# W5500.net
KiCad netlist of a schematic drawn in Altium Designer
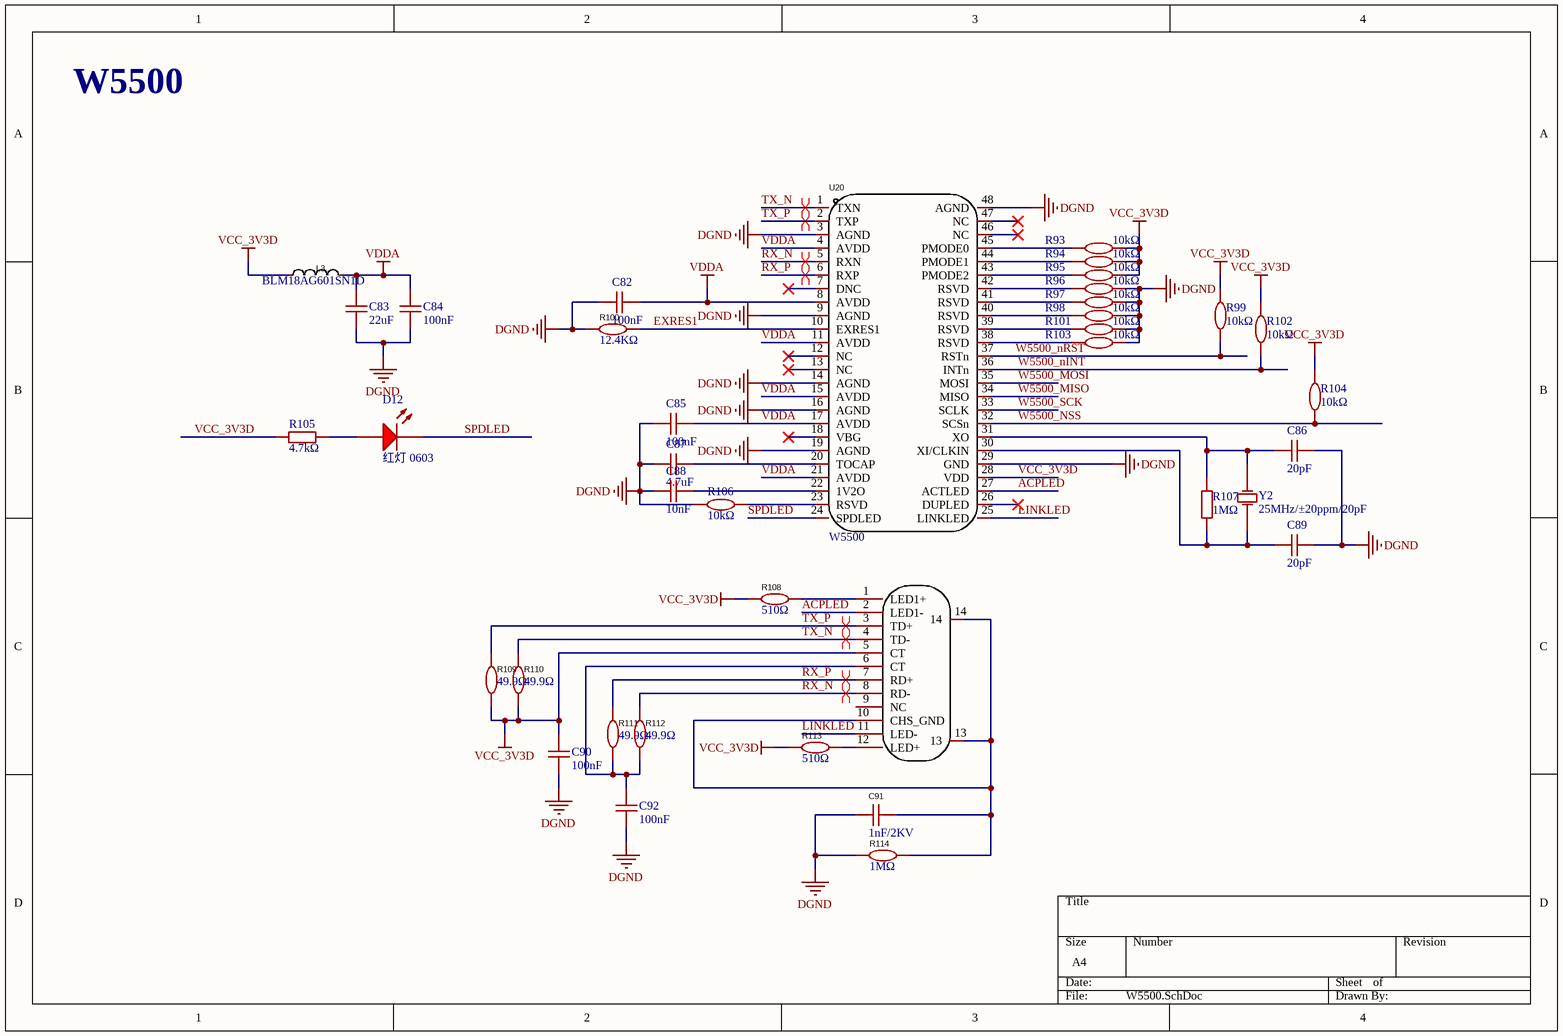
[diagram p0: W5500.SchDoc]

(export (version "E")
  (design (tool "Eeschema 10.0.6"))
  (components
    (comp (ref "C82")
      (value "100nF")
      (footprint "C0402")
      (description "贴片电容,X7R")
      (libsource (lib "XG_DW_POCT_2K10LED_3") (part "100nF/50V,C0402"))
    )
    (comp (ref "C83")
      (value "22uF")
      (footprint "C0603")
      (description "贴片电容,X7R")
      (libsource (lib "XG_DW_POCT_2K10LED_3") (part "22uF/50V,C0603"))
    )
    (comp (ref "C84")
      (value "100nF")
      (footprint "C0402")
      (description "贴片电容,X7R")
      (libsource (lib "XG_DW_POCT_2K10LED_3") (part "100nF/50V,C0402"))
    )
    (comp (ref "C85")
      (value "100nF")
      (footprint "C0402")
      (description "贴片电容,X7R")
      (libsource (lib "XG_DW_POCT_2K10LED_3") (part "100nF/50V,C0402"))
    )
    (comp (ref "C86")
      (value "20pF")
      (footprint "C0603")
      (description "贴片电容,X7R")
      (libsource (lib "XG_DW_POCT_2K10LED_3") (part "20pF/50V,C0603"))
    )
    (comp (ref "C87")
      (value "4.7uF")
      (footprint "C0402")
      (description "贴片电容,X7R")
      (libsource (lib "XG_DW_POCT_2K10LED_3") (part "4.7uF/50V,C0402"))
    )
    (comp (ref "C88")
      (value "10nF")
      (footprint "C0402")
      (description "贴片电容,X7R")
      (libsource (lib "XG_DW_POCT_2K10LED_3") (part "10nF/50V,C0402"))
    )
    (comp (ref "C89")
      (value "20pF")
      (footprint "C0603")
      (description "贴片电容,X7R")
      (libsource (lib "XG_DW_POCT_2K10LED_3") (part "20pF/50V,C0603"))
    )
    (comp (ref "C90")
      (value "100nF")
      (footprint "C0402")
      (description "贴片电容,X7R")
      (libsource (lib "XG_DW_POCT_2K10LED_3") (part "100nF/50V,C0402"))
    )
    (comp (ref "C91")
      (value "1nF/2KV")
      (footprint "C1206")
      (description "贴片电容,X7R")
      (libsource (lib "XG_DW_POCT_2K10LED_3") (part "1nF/2KV,C1206"))
    )
    (comp (ref "C92")
      (value "100nF")
      (footprint "C0402")
      (description "贴片电容,X7R")
      (libsource (lib "XG_DW_POCT_2K10LED_3") (part "100nF/50V,C0402"))
    )
    (comp (ref "D12")
      (value "红灯 0603")
      (footprint "LED_0603")
      (description "发光二极管")
      (libsource (lib "XG_DW_POCT_2K10LED_3") (part "红灯 0603"))
    )
    (comp (ref "L3")
      (value "BLM18AG601SN1D")
      (footprint "L0603")
      (fields (field (name "MANUFACTURER") "muRata(村田)") (field (name "TOLERANCE") "±25%"))
      (libsource (lib "altium-import") (part "root_0_BLM18AG601SN1D_"))
    )
    (comp (ref "R93")
      (value "10kΩ")
      (footprint "R0402")
      (description "电阻类型:厚膜电阻;阻值:10kΩ;精度:±1%;功率:100mW;最大工作电压:75V;温度系数:±100ppm/℃;")
      (libsource (lib "XG_DW_POCT_2K10LED_3") (part "10kΩ,R0402"))
    )
    (comp (ref "R94")
      (value "10kΩ")
      (footprint "R0402")
      (description "电阻类型:厚膜电阻;阻值:10kΩ;精度:±1%;功率:100mW;最大工作电压:75V;温度系数:±100ppm/℃;")
      (libsource (lib "XG_DW_POCT_2K10LED_3") (part "10kΩ,R0402"))
    )
    (comp (ref "R95")
      (value "10kΩ")
      (footprint "R0402")
      (description "电阻类型:厚膜电阻;阻值:10kΩ;精度:±1%;功率:100mW;最大工作电压:75V;温度系数:±100ppm/℃;")
      (libsource (lib "XG_DW_POCT_2K10LED_3") (part "10kΩ,R0402"))
    )
    (comp (ref "R96")
      (value "10kΩ")
      (footprint "R0402")
      (description "电阻类型:厚膜电阻;阻值:10kΩ;精度:±1%;功率:100mW;最大工作电压:75V;温度系数:±100ppm/℃;")
      (libsource (lib "XG_DW_POCT_2K10LED_3") (part "10kΩ,R0402"))
    )
    (comp (ref "R97")
      (value "10kΩ")
      (footprint "R0402")
      (description "电阻类型:厚膜电阻;阻值:10kΩ;精度:±1%;功率:100mW;最大工作电压:75V;温度系数:±100ppm/℃;")
      (libsource (lib "XG_DW_POCT_2K10LED_3") (part "10kΩ,R0402"))
    )
    (comp (ref "R98")
      (value "10kΩ")
      (footprint "R0402")
      (description "电阻类型:厚膜电阻;阻值:10kΩ;精度:±1%;功率:100mW;最大工作电压:75V;温度系数:±100ppm/℃;")
      (libsource (lib "XG_DW_POCT_2K10LED_3") (part "10kΩ,R0402"))
    )
    (comp (ref "R99")
      (value "10kΩ")
      (footprint "R0402")
      (description "电阻类型:厚膜电阻;阻值:10kΩ;精度:±1%;功率:100mW;最大工作电压:75V;温度系数:±100ppm/℃;")
      (libsource (lib "XG_DW_POCT_2K10LED_3") (part "10kΩ,R0402"))
    )
    (comp (ref "R100")
      (value "12.4KΩ")
      (footprint "R0402")
      (description "贴片电阻12.4KΩ;1%")
      (libsource (lib "XG_DW_POCT_2K10LED_3") (part "12.4KΩ,R0402"))
    )
    (comp (ref "R101")
      (value "10kΩ")
      (footprint "R0402")
      (description "电阻类型:厚膜电阻;阻值:10kΩ;精度:±1%;功率:100mW;最大工作电压:75V;温度系数:±100ppm/℃;")
      (libsource (lib "XG_DW_POCT_2K10LED_3") (part "10kΩ,R0402"))
    )
    (comp (ref "R102")
      (value "10kΩ")
      (footprint "R0402")
      (description "电阻类型:厚膜电阻;阻值:10kΩ;精度:±1%;功率:100mW;最大工作电压:75V;温度系数:±100ppm/℃;")
      (libsource (lib "XG_DW_POCT_2K10LED_3") (part "10kΩ,R0402"))
    )
    (comp (ref "R103")
      (value "10kΩ")
      (footprint "R0402")
      (description "电阻类型:厚膜电阻;阻值:10kΩ;精度:±1%;功率:100mW;最大工作电压:75V;温度系数:±100ppm/℃;")
      (libsource (lib "XG_DW_POCT_2K10LED_3") (part "10kΩ,R0402"))
    )
    (comp (ref "R104")
      (value "10kΩ")
      (footprint "R0402")
      (description "电阻类型:厚膜电阻;阻值:10kΩ;精度:±1%;功率:100mW;最大工作电压:75V;温度系数:±100ppm/℃;")
      (libsource (lib "XG_DW_POCT_2K10LED_3") (part "10kΩ,R0402"))
    )
    (comp (ref "R105")
      (value "4.7kΩ")
      (footprint "R0603")
      (description "贴片电阻")
      (libsource (lib "XG_DW_POCT_2K10LED_3") (part "4.7kΩ,R0603"))
    )
    (comp (ref "R106")
      (value "10kΩ")
      (footprint "R0402")
      (description "电阻类型:厚膜电阻;阻值:10kΩ;精度:±1%;功率:100mW;最大工作电压:75V;温度系数:±100ppm/℃;")
      (libsource (lib "XG_DW_POCT_2K10LED_3") (part "10kΩ,R0402"))
    )
    (comp (ref "R107")
      (value "1MΩ")
      (footprint "R0603")
      (description "贴片电阻")
      (libsource (lib "XG_DW_POCT_2K10LED_3") (part "1MΩ,R0603"))
    )
    (comp (ref "R108")
      (value "510Ω")
      (footprint "R0402")
      (description "贴片电阻")
      (libsource (lib "XG_DW_POCT_2K10LED_3") (part "510Ω,R0402"))
    )
    (comp (ref "R109")
      (value "49.9Ω")
      (footprint "R0402")
      (description "贴片电阻49.9R;1%")
      (libsource (lib "XG_DW_POCT_2K10LED_3") (part "49.9Ω,R0402"))
    )
    (comp (ref "R110")
      (value "49.9Ω")
      (footprint "R0402")
      (description "贴片电阻49.9R;1%")
      (libsource (lib "XG_DW_POCT_2K10LED_3") (part "49.9Ω,R0402"))
    )
    (comp (ref "R111")
      (value "49.9Ω")
      (footprint "R0402")
      (description "贴片电阻49.9R;1%")
      (libsource (lib "XG_DW_POCT_2K10LED_3") (part "49.9Ω,R0402"))
    )
    (comp (ref "R112")
      (value "49.9Ω")
      (footprint "R0402")
      (description "贴片电阻49.9R;1%")
      (libsource (lib "XG_DW_POCT_2K10LED_3") (part "49.9Ω,R0402"))
    )
    (comp (ref "R113")
      (value "510Ω")
      (footprint "R0402")
      (description "贴片电阻")
      (libsource (lib "XG_DW_POCT_2K10LED_3") (part "510Ω,R0402"))
    )
    (comp (ref "R114")
      (value "1MΩ")
      (footprint "R0402")
      (description "电阻类型:厚膜电阻;阻值:1MΩ;精度:±1%;功率:100mW;最大工作电压:75V;温度系数:±100ppm/℃;")
      (libsource (lib "XG_DW_POCT_2K10LED_3") (part "1MΩ,R0402"))
    )
    (comp (ref "RJ1")
      (value "HR961160C")
      (footprint "RJ45-SMD_HR961160C")
      (libsource (lib "XG_DW_POCT_2K10LED_3") (part "HR961160C"))
    )
    (comp (ref "U20")
      (value "W5500")
      (footprint "LQFP-48_L7.0-W7.0-P0.50-LS9.0-BL")
      (libsource (lib "XG_DW_POCT_2K10LED_3") (part "W5500"))
    )
    (comp (ref "Y2")
      (value "25MHz/±20ppm/20pF")
      (footprint "SMD-5032_2P")
      (description "X503225MSB2GI;无源晶振")
      (libsource (lib "XG_DW_POCT_2K10LED_3") (part "25MHz/±20ppm/20pF,SMD5032"))
    )
  )
  (nets
    (net (code "1") (name "/ACPLED") (class "Default")
      (node (ref "RJ1") (pin "2") (pinfunction "LED1-_2") (pintype "passive"))
      (node (ref "U20") (pin "27") (pinfunction "ACTLED_27") (pintype "passive"))
    )
    (net (code "2") (name "/EXRES1") (class "Default")
      (node (ref "R100") (pin "2") (pinfunction "2_2") (pintype "passive"))
      (node (ref "U20") (pin "10") (pinfunction "EXRES1_10") (pintype "passive"))
    )
    (net (code "3") (name "/LINKLED") (class "Default")
      (node (ref "RJ1") (pin "11") (pinfunction "LED-_11") (pintype "passive"))
      (node (ref "U20") (pin "25") (pinfunction "LINKLED_25") (pintype "passive"))
    )
    (net (code "4") (name "/RX_N") (class "Default")
      (node (ref "R112") (pin "2") (pinfunction "2_2") (pintype "passive"))
      (node (ref "RJ1") (pin "8") (pinfunction "RD-_8") (pintype "passive"))
      (node (ref "U20") (pin "5") (pinfunction "RXN_5") (pintype "passive"))
    )
    (net (code "5") (name "/RX_P") (class "Default")
      (node (ref "R111") (pin "2") (pinfunction "2_2") (pintype "passive"))
      (node (ref "RJ1") (pin "7") (pinfunction "RD+_7") (pintype "passive"))
      (node (ref "U20") (pin "6") (pinfunction "RXP_6") (pintype "passive"))
    )
    (net (code "6") (name "/SPDLED") (class "Default")
      (node (ref "D12") (pin "K") (pinfunction "K_K") (pintype "passive"))
      (node (ref "U20") (pin "24") (pinfunction "SPDLED_24") (pintype "passive"))
    )
    (net (code "7") (name "/TX_N") (class "Default")
      (node (ref "R110") (pin "2") (pinfunction "2_2") (pintype "passive"))
      (node (ref "RJ1") (pin "4") (pinfunction "TD-_4") (pintype "passive"))
      (node (ref "U20") (pin "1") (pinfunction "TXN_1") (pintype "passive"))
    )
    (net (code "8") (name "/TX_P") (class "Default")
      (node (ref "R109") (pin "2") (pinfunction "2_2") (pintype "passive"))
      (node (ref "RJ1") (pin "3") (pinfunction "TD+_3") (pintype "passive"))
      (node (ref "U20") (pin "2") (pinfunction "TXP_2") (pintype "passive"))
    )
    (net (code "9") (name "/W5500_MISO") (class "Default")
      (node (ref "U20") (pin "34") (pinfunction "MISO_34") (pintype "passive"))
    )
    (net (code "10") (name "/W5500_MOSI") (class "Default")
      (node (ref "U20") (pin "35") (pinfunction "MOSI_35") (pintype "passive"))
    )
    (net (code "11") (name "/W5500_NSS") (class "Default")
      (node (ref "R104") (pin "2") (pinfunction "2_2") (pintype "passive"))
      (node (ref "U20") (pin "32") (pinfunction "SCSn_32") (pintype "passive"))
    )
    (net (code "12") (name "/W5500_SCK") (class "Default")
      (node (ref "U20") (pin "33") (pinfunction "SCLK_33") (pintype "passive"))
    )
    (net (code "13") (name "/W5500_nINT") (class "Default")
      (node (ref "R102") (pin "2") (pinfunction "2_2") (pintype "passive"))
      (node (ref "U20") (pin "36") (pinfunction "INTn_36") (pintype "passive"))
    )
    (net (code "14") (name "/W5500_nRST") (class "Default")
      (node (ref "R99") (pin "2") (pinfunction "2_2") (pintype "passive"))
      (node (ref "U20") (pin "37") (pinfunction "RSTn_37") (pintype "passive"))
    )
    (net (code "15") (name "DGND") (class "Default")
      (node (ref "C82") (pin "1") (pinfunction "1_1") (pintype "passive"))
      (node (ref "C83") (pin "1") (pinfunction "1_1") (pintype "passive"))
      (node (ref "C84") (pin "1") (pinfunction "1_1") (pintype "passive"))
      (node (ref "C85") (pin "1") (pinfunction "1_1") (pintype "passive"))
      (node (ref "C86") (pin "2") (pinfunction "2_2") (pintype "passive"))
      (node (ref "C87") (pin "1") (pinfunction "1_1") (pintype "passive"))
      (node (ref "C88") (pin "1") (pinfunction "1_1") (pintype "passive"))
      (node (ref "C89") (pin "2") (pinfunction "2_2") (pintype "passive"))
      (node (ref "C90") (pin "1") (pinfunction "1_1") (pintype "passive"))
      (node (ref "C91") (pin "1") (pinfunction "1_1") (pintype "passive"))
      (node (ref "C92") (pin "1") (pinfunction "1_1") (pintype "passive"))
      (node (ref "R100") (pin "1") (pinfunction "1_1") (pintype "passive"))
      (node (ref "R101") (pin "1") (pinfunction "1_1") (pintype "passive"))
      (node (ref "R103") (pin "1") (pinfunction "1_1") (pintype "passive"))
      (node (ref "R106") (pin "2") (pinfunction "2_2") (pintype "passive"))
      (node (ref "R114") (pin "1") (pinfunction "1_1") (pintype "passive"))
      (node (ref "R96") (pin "1") (pinfunction "1_1") (pintype "passive"))
      (node (ref "R97") (pin "1") (pinfunction "1_1") (pintype "passive"))
      (node (ref "R98") (pin "1") (pinfunction "1_1") (pintype "passive"))
      (node (ref "U20") (pin "14") (pinfunction "AGND_14") (pintype "passive"))
      (node (ref "U20") (pin "16") (pinfunction "AGND_16") (pintype "passive"))
      (node (ref "U20") (pin "19") (pinfunction "AGND_19") (pintype "passive"))
      (node (ref "U20") (pin "29") (pinfunction "GND_29") (pintype "passive"))
      (node (ref "U20") (pin "3") (pinfunction "AGND_3") (pintype "passive"))
      (node (ref "U20") (pin "48") (pinfunction "AGND_48") (pintype "passive"))
      (node (ref "U20") (pin "9") (pinfunction "AGND_9") (pintype "passive"))
    )
    (net (code "16") (name "Net-(C92-Pad2)") (class "Default")
      (node (ref "C92") (pin "2") (pinfunction "2_2") (pintype "passive"))
      (node (ref "R111") (pin "1") (pinfunction "1_1") (pintype "passive"))
      (node (ref "R112") (pin "1") (pinfunction "1_1") (pintype "passive"))
      (node (ref "RJ1") (pin "6") (pinfunction "CT_6") (pintype "passive"))
    )
    (net (code "17") (name "Net-(D12-PadA)") (class "Default")
      (node (ref "D12") (pin "A") (pinfunction "A_A") (pintype "passive"))
      (node (ref "R105") (pin "1") (pinfunction "1_1") (pintype "passive"))
    )
    (net (code "18") (name "Net-(R96-Pad2)") (class "Default")
      (node (ref "R96") (pin "2") (pinfunction "2_2") (pintype "passive"))
      (node (ref "U20") (pin "42") (pinfunction "RSVD_42") (pintype "passive"))
    )
    (net (code "19") (name "Net-(R97-Pad2)") (class "Default")
      (node (ref "R97") (pin "2") (pinfunction "2_2") (pintype "passive"))
      (node (ref "U20") (pin "41") (pinfunction "RSVD_41") (pintype "passive"))
    )
    (net (code "20") (name "Net-(R98-Pad2)") (class "Default")
      (node (ref "R98") (pin "2") (pinfunction "2_2") (pintype "passive"))
      (node (ref "U20") (pin "40") (pinfunction "RSVD_40") (pintype "passive"))
    )
    (net (code "21") (name "Net-(R101-Pad2)") (class "Default")
      (node (ref "R101") (pin "2") (pinfunction "2_2") (pintype "passive"))
      (node (ref "U20") (pin "39") (pinfunction "RSVD_39") (pintype "passive"))
    )
    (net (code "22") (name "Net-(R103-Pad2)") (class "Default")
      (node (ref "R103") (pin "2") (pinfunction "2_2") (pintype "passive"))
      (node (ref "U20") (pin "38") (pinfunction "RSVD_38") (pintype "passive"))
    )
    (net (code "23") (name "Net-(R106-Pad1)") (class "Default")
      (node (ref "R106") (pin "1") (pinfunction "1_1") (pintype "passive"))
      (node (ref "U20") (pin "23") (pinfunction "RSVD_23") (pintype "passive"))
    )
    (net (code "24") (name "Net-(RJ1-CHS_GND)") (class "Default")
      (node (ref "C91") (pin "2") (pinfunction "2_2") (pintype "passive"))
      (node (ref "R114") (pin "2") (pinfunction "2_2") (pintype "passive"))
      (node (ref "RJ1") (pin "10") (pinfunction "CHS_GND_10") (pintype "passive"))
      (node (ref "RJ1") (pin "13") (pinfunction "13_13") (pintype "passive"))
      (node (ref "RJ1") (pin "14") (pinfunction "14_14") (pintype "passive"))
    )
    (net (code "25") (name "Net-(RJ1-LED+)") (class "Default")
      (node (ref "R113") (pin "1") (pinfunction "1_1") (pintype "passive"))
      (node (ref "RJ1") (pin "12") (pinfunction "LED+_12") (pintype "passive"))
    )
    (net (code "26") (name "Net-(RJ1-LED1+)") (class "Default")
      (node (ref "R108") (pin "1") (pinfunction "1_1") (pintype "passive"))
      (node (ref "RJ1") (pin "1") (pinfunction "LED1+_1") (pintype "passive"))
    )
    (net (code "27") (name "Net-(U20-1V2O)") (class "Default")
      (node (ref "C88") (pin "2") (pinfunction "2_2") (pintype "passive"))
      (node (ref "U20") (pin "22") (pinfunction "1V2O_22") (pintype "passive"))
    )
    (net (code "28") (name "Net-(U20-PMODE0)") (class "Default")
      (node (ref "R93") (pin "2") (pinfunction "2_2") (pintype "passive"))
      (node (ref "U20") (pin "45") (pinfunction "PMODE0_45") (pintype "passive"))
    )
    (net (code "29") (name "Net-(U20-PMODE1)") (class "Default")
      (node (ref "R94") (pin "2") (pinfunction "2_2") (pintype "passive"))
      (node (ref "U20") (pin "44") (pinfunction "PMODE1_44") (pintype "passive"))
    )
    (net (code "30") (name "Net-(U20-PMODE2)") (class "Default")
      (node (ref "R95") (pin "2") (pinfunction "2_2") (pintype "passive"))
      (node (ref "U20") (pin "43") (pinfunction "PMODE2_43") (pintype "passive"))
    )
    (net (code "31") (name "Net-(U20-TOCAP)") (class "Default")
      (node (ref "C87") (pin "2") (pinfunction "2_2") (pintype "passive"))
      (node (ref "U20") (pin "20") (pinfunction "TOCAP_20") (pintype "passive"))
    )
    (net (code "32") (name "Net-(U20-XI{slash}CLKIN)") (class "Default")
      (node (ref "C89") (pin "1") (pinfunction "1_1") (pintype "passive"))
      (node (ref "R107") (pin "1") (pinfunction "1_1") (pintype "passive"))
      (node (ref "U20") (pin "30") (pinfunction "XI/CLKIN_30") (pintype "passive"))
      (node (ref "Y2") (pin "1") (pinfunction "OSC1_1") (pintype "passive"))
    )
    (net (code "33") (name "Net-(U20-XO)") (class "Default")
      (node (ref "C86") (pin "1") (pinfunction "1_1") (pintype "passive"))
      (node (ref "R107") (pin "2") (pinfunction "2_2") (pintype "passive"))
      (node (ref "U20") (pin "31") (pinfunction "XO_31") (pintype "passive"))
      (node (ref "Y2") (pin "2") (pinfunction "OSC2_2") (pintype "passive"))
    )
    (net (code "34") (name "VCC_3V3D") (class "Default")
      (node (ref "C90") (pin "2") (pinfunction "2_2") (pintype "passive"))
      (node (ref "L3") (pin "1") (pinfunction "1_1") (pintype "passive"))
      (node (ref "R102") (pin "1") (pinfunction "1_1") (pintype "passive"))
      (node (ref "R104") (pin "1") (pinfunction "1_1") (pintype "passive"))
      (node (ref "R105") (pin "2") (pinfunction "2_2") (pintype "passive"))
      (node (ref "R108") (pin "2") (pinfunction "2_2") (pintype "passive"))
      (node (ref "R109") (pin "1") (pinfunction "1_1") (pintype "passive"))
      (node (ref "R110") (pin "1") (pinfunction "1_1") (pintype "passive"))
      (node (ref "R113") (pin "2") (pinfunction "2_2") (pintype "passive"))
      (node (ref "R93") (pin "1") (pinfunction "1_1") (pintype "passive"))
      (node (ref "R94") (pin "1") (pinfunction "1_1") (pintype "passive"))
      (node (ref "R95") (pin "1") (pinfunction "1_1") (pintype "passive"))
      (node (ref "R99") (pin "1") (pinfunction "1_1") (pintype "passive"))
      (node (ref "RJ1") (pin "5") (pinfunction "CT_5") (pintype "passive"))
      (node (ref "U20") (pin "28") (pinfunction "VDD_28") (pintype "passive"))
    )
    (net (code "35") (name "VDDA") (class "Default")
      (node (ref "C82") (pin "2") (pinfunction "2_2") (pintype "passive"))
      (node (ref "C83") (pin "2") (pinfunction "2_2") (pintype "passive"))
      (node (ref "C84") (pin "2") (pinfunction "2_2") (pintype "passive"))
      (node (ref "C85") (pin "2") (pinfunction "2_2") (pintype "passive"))
      (node (ref "L3") (pin "2") (pinfunction "2_2") (pintype "passive"))
      (node (ref "U20") (pin "11") (pinfunction "AVDD_11") (pintype "passive"))
      (node (ref "U20") (pin "15") (pinfunction "AVDD_15") (pintype "passive"))
      (node (ref "U20") (pin "17") (pinfunction "AVDD_17") (pintype "passive"))
      (node (ref "U20") (pin "21") (pinfunction "AVDD_21") (pintype "passive"))
      (node (ref "U20") (pin "4") (pinfunction "AVDD_4") (pintype "passive"))
      (node (ref "U20") (pin "8") (pinfunction "AVDD_8") (pintype "passive"))
    )
    (net (code "36") (name "unconnected-(RJ1-NC-Pad9)") (class "Default")
      (node (ref "RJ1") (pin "9") (pinfunction "NC_9") (pintype "passive"))
    )
    (net (code "37") (name "unconnected-(U20-DNC-Pad7)") (class "Default")
      (node (ref "U20") (pin "7") (pinfunction "DNC_7") (pintype "passive+no_connect"))
    )
    (net (code "38") (name "unconnected-(U20-DUPLED-Pad26)") (class "Default")
      (node (ref "U20") (pin "26") (pinfunction "DUPLED_26") (pintype "passive+no_connect"))
    )
    (net (code "39") (name "unconnected-(U20-NC-Pad12)") (class "Default")
      (node (ref "U20") (pin "12") (pinfunction "NC_12") (pintype "passive+no_connect"))
    )
    (net (code "40") (name "unconnected-(U20-NC-Pad13)") (class "Default")
      (node (ref "U20") (pin "13") (pinfunction "NC_13") (pintype "passive+no_connect"))
    )
    (net (code "41") (name "unconnected-(U20-NC-Pad46)") (class "Default")
      (node (ref "U20") (pin "46") (pinfunction "NC_46") (pintype "passive+no_connect"))
    )
    (net (code "42") (name "unconnected-(U20-NC-Pad47)") (class "Default")
      (node (ref "U20") (pin "47") (pinfunction "NC_47") (pintype "passive+no_connect"))
    )
    (net (code "43") (name "unconnected-(U20-VBG-Pad18)") (class "Default")
      (node (ref "U20") (pin "18") (pinfunction "VBG_18") (pintype "passive+no_connect"))
    )
  )
)
